# Project.net
KiCad netlist of a schematic drawn in EAGLE
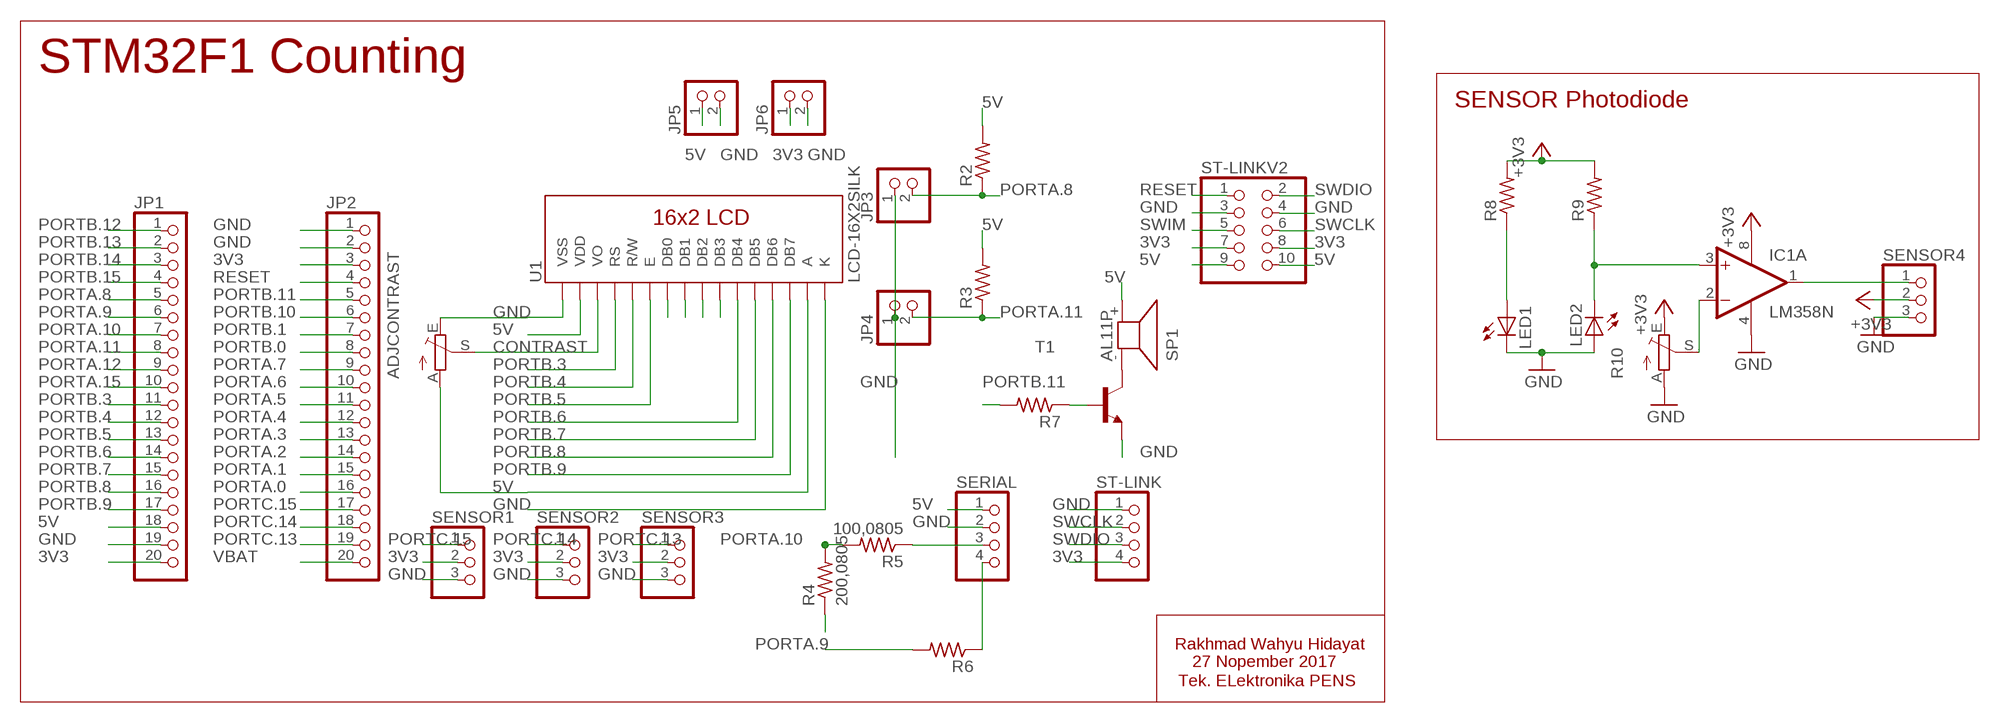
[diagram p0: schematic, sheet 1]

(export (version "E")
  (design (tool "Eeschema 10.0.6"))
  (components
    (comp (ref "ADJCONTRAST")
      (value "TRIM_EU-CA6V")
      (footprint "eagle-import:CA6V")
      (libsource (lib "eagle-import") (part "TRIM_EU-CA6V"))
    )
    (comp (ref "IC1")
      (value "LM358N")
      (footprint "eagle-import:DIL08")
      (libsource (lib "eagle-import") (part "LM358N"))
    )
    (comp (ref "JP1")
      (value "PINHD-1X20")
      (footprint "eagle-import:1X20")
      (libsource (lib "eagle-import") (part "PINHD-1X20"))
    )
    (comp (ref "JP2")
      (value "PINHD-1X20")
      (footprint "eagle-import:1X20")
      (libsource (lib "eagle-import") (part "PINHD-1X20"))
    )
    (comp (ref "JP3")
      (value "PINHD-1X2")
      (footprint "eagle-import:1X02")
      (libsource (lib "eagle-import") (part "PINHD-1X2"))
    )
    (comp (ref "JP4")
      (value "PINHD-1X2")
      (footprint "eagle-import:1X02")
      (libsource (lib "eagle-import") (part "PINHD-1X2"))
    )
    (comp (ref "JP5")
      (value "PINHD-1X2")
      (footprint "eagle-import:1X02")
      (libsource (lib "eagle-import") (part "PINHD-1X2"))
    )
    (comp (ref "JP6")
      (value "PINHD-1X2")
      (footprint "eagle-import:1X02")
      (libsource (lib "eagle-import") (part "PINHD-1X2"))
    )
    (comp (ref "LED1")
      (value "LED3MM")
      (footprint "eagle-import:LED3MM")
      (libsource (lib "eagle-import") (part "LED3MM"))
    )
    (comp (ref "LED2")
      (value "LED3MM")
      (footprint "eagle-import:LED3MM")
      (libsource (lib "eagle-import") (part "LED3MM"))
    )
    (comp (ref "R2")
      (value "R-US_M0805")
      (footprint "eagle-import:M0805")
      (libsource (lib "eagle-import") (part "R-US_M0805"))
    )
    (comp (ref "R3")
      (value "R-US_M0805")
      (footprint "eagle-import:M0805")
      (libsource (lib "eagle-import") (part "R-US_M0805"))
    )
    (comp (ref "R4")
      (value "200,0805")
      (footprint "eagle-import:M0805")
      (libsource (lib "eagle-import") (part "R-US_M0805"))
    )
    (comp (ref "R5")
      (value "100,0805")
      (footprint "eagle-import:M0805")
      (libsource (lib "eagle-import") (part "R-US_M0805"))
    )
    (comp (ref "R6")
      (value "R-US_M0805")
      (footprint "eagle-import:M0805")
      (libsource (lib "eagle-import") (part "R-US_M0805"))
    )
    (comp (ref "R7")
      (value "R-US_M0805")
      (footprint "eagle-import:M0805")
      (libsource (lib "eagle-import") (part "R-US_M0805"))
    )
    (comp (ref "R8")
      (value "R-US_0204/7")
      (footprint "eagle-import:0204_7")
      (libsource (lib "eagle-import") (part "R-US_0204/7"))
    )
    (comp (ref "R9")
      (value "R-US_0204/7")
      (footprint "eagle-import:0204_7")
      (libsource (lib "eagle-import") (part "R-US_0204/7"))
    )
    (comp (ref "R10")
      (value "TRIM_EU-CA6V")
      (footprint "eagle-import:CA6V")
      (libsource (lib "eagle-import") (part "TRIM_EU-CA6V"))
    )
    (comp (ref "SENSOR1")
      (value "PINHD-1X3")
      (footprint "eagle-import:1X03")
      (libsource (lib "eagle-import") (part "PINHD-1X3"))
    )
    (comp (ref "SENSOR2")
      (value "PINHD-1X3")
      (footprint "eagle-import:1X03")
      (libsource (lib "eagle-import") (part "PINHD-1X3"))
    )
    (comp (ref "SENSOR3")
      (value "PINHD-1X3")
      (footprint "eagle-import:1X03")
      (libsource (lib "eagle-import") (part "PINHD-1X3"))
    )
    (comp (ref "SENSOR4")
      (value "PINHD-1X3")
      (footprint "eagle-import:1X03")
      (libsource (lib "eagle-import") (part "PINHD-1X3"))
    )
    (comp (ref "SERIAL")
      (value "PINHD-1X4")
      (footprint "eagle-import:1X04")
      (libsource (lib "eagle-import") (part "PINHD-1X4"))
    )
    (comp (ref "SP1")
      (value "AL11P")
      (footprint "eagle-import:AL11P")
      (libsource (lib "eagle-import") (part "AL11P"))
    )
    (comp (ref "ST-LINK")
      (value "PINHD-1X4")
      (footprint "eagle-import:1X04")
      (libsource (lib "eagle-import") (part "PINHD-1X4"))
    )
    (comp (ref "ST-LINKV2")
      (value "PINHD-2X5")
      (footprint "eagle-import:2X05")
      (libsource (lib "eagle-import") (part "PINHD-2X5"))
    )
    (comp (ref "T1")
      (value "-NPN-SOT23-EBC")
      (footprint "eagle-import:SOT23-EBC")
      (libsource (lib "eagle-import") (part "-NPN-SOT23-EBC"))
    )
    (comp (ref "U1")
      (value "LCD-16X2SILK")
      (footprint "eagle-import:LCD-16X2")
      (libsource (lib "eagle-import") (part "LCD-16X2SILK"))
    )
  )
  (nets
    (net (code "1") (name "+3V3") (class "Default")
      (node (ref "IC1") (pin "8") (pinfunction "V+_8") (pintype "power_in"))
      (node (ref "R10") (pin "E") (pinfunction "E_E") (pintype "passive"))
      (node (ref "R8") (pin "2") (pinfunction "2_2") (pintype "passive"))
      (node (ref "R9") (pin "2") (pinfunction "2_2") (pintype "passive"))
      (node (ref "SENSOR4") (pin "2") (pinfunction "2_2") (pintype "passive"))
    )
    (net (code "2") (name "/3V3") (class "Default")
      (node (ref "JP1") (pin "20") (pinfunction "20_20") (pintype "passive"))
      (node (ref "JP2") (pin "3") (pinfunction "3_3") (pintype "passive"))
      (node (ref "JP6") (pin "1") (pinfunction "1_1") (pintype "passive"))
      (node (ref "SENSOR1") (pin "2") (pinfunction "2_2") (pintype "passive"))
      (node (ref "SENSOR2") (pin "2") (pinfunction "2_2") (pintype "passive"))
      (node (ref "SENSOR3") (pin "2") (pinfunction "2_2") (pintype "passive"))
      (node (ref "ST-LINK") (pin "4") (pinfunction "4_4") (pintype "passive"))
      (node (ref "ST-LINKV2") (pin "7") (pinfunction "7_7") (pintype "passive"))
      (node (ref "ST-LINKV2") (pin "8") (pinfunction "8_8") (pintype "passive"))
    )
    (net (code "3") (name "/5V") (class "Default")
      (node (ref "ADJCONTRAST") (pin "A") (pinfunction "A_A") (pintype "passive"))
      (node (ref "JP1") (pin "18") (pinfunction "18_18") (pintype "passive"))
      (node (ref "JP5") (pin "1") (pinfunction "1_1") (pintype "passive"))
      (node (ref "R2") (pin "2") (pinfunction "2_2") (pintype "passive"))
      (node (ref "R3") (pin "2") (pinfunction "2_2") (pintype "passive"))
      (node (ref "SERIAL") (pin "1") (pinfunction "1_1") (pintype "passive"))
      (node (ref "SP1") (pin "+") (pinfunction "2_+") (pintype "passive"))
      (node (ref "ST-LINKV2") (pin "10") (pinfunction "10_10") (pintype "passive"))
      (node (ref "ST-LINKV2") (pin "9") (pinfunction "9_9") (pintype "passive"))
      (node (ref "U1") (pin "15") (pinfunction "A_15") (pintype "power_in"))
      (node (ref "U1") (pin "2") (pinfunction "VDD_2") (pintype "power_in"))
    )
    (net (code "4") (name "/CONTRAST") (class "Default")
      (node (ref "ADJCONTRAST") (pin "S") (pinfunction "S_S") (pintype "passive"))
      (node (ref "U1") (pin "3") (pinfunction "VO_3") (pintype "bidirectional"))
    )
    (net (code "5") (name "/PORTA.0") (class "Default")
      (node (ref "JP2") (pin "16") (pinfunction "16_16") (pintype "passive"))
    )
    (net (code "6") (name "/PORTA.1") (class "Default")
      (node (ref "JP2") (pin "15") (pinfunction "15_15") (pintype "passive"))
    )
    (net (code "7") (name "/PORTA.2") (class "Default")
      (node (ref "JP2") (pin "14") (pinfunction "14_14") (pintype "passive"))
    )
    (net (code "8") (name "/PORTA.3") (class "Default")
      (node (ref "JP2") (pin "13") (pinfunction "13_13") (pintype "passive"))
    )
    (net (code "9") (name "/PORTA.4") (class "Default")
      (node (ref "JP2") (pin "12") (pinfunction "12_12") (pintype "passive"))
    )
    (net (code "10") (name "/PORTA.5") (class "Default")
      (node (ref "JP2") (pin "11") (pinfunction "11_11") (pintype "passive"))
    )
    (net (code "11") (name "/PORTA.6") (class "Default")
      (node (ref "JP2") (pin "10") (pinfunction "10_10") (pintype "passive"))
    )
    (net (code "12") (name "/PORTA.7") (class "Default")
      (node (ref "JP2") (pin "9") (pinfunction "9_9") (pintype "passive"))
    )
    (net (code "13") (name "/PORTA.8") (class "Default")
      (node (ref "JP1") (pin "5") (pinfunction "5_5") (pintype "passive"))
      (node (ref "JP3") (pin "2") (pinfunction "2_2") (pintype "passive"))
      (node (ref "R2") (pin "1") (pinfunction "1_1") (pintype "passive"))
    )
    (net (code "14") (name "/PORTA.9") (class "Default")
      (node (ref "JP1") (pin "6") (pinfunction "6_6") (pintype "passive"))
      (node (ref "R6") (pin "2") (pinfunction "2_2") (pintype "passive"))
    )
    (net (code "15") (name "/PORTA.10") (class "Default")
      (node (ref "JP1") (pin "7") (pinfunction "7_7") (pintype "passive"))
      (node (ref "R4") (pin "2") (pinfunction "2_2") (pintype "passive"))
      (node (ref "R5") (pin "2") (pinfunction "2_2") (pintype "passive"))
    )
    (net (code "16") (name "/PORTA.11") (class "Default")
      (node (ref "JP1") (pin "8") (pinfunction "8_8") (pintype "passive"))
      (node (ref "JP4") (pin "2") (pinfunction "2_2") (pintype "passive"))
      (node (ref "R3") (pin "1") (pinfunction "1_1") (pintype "passive"))
    )
    (net (code "17") (name "/PORTA.12") (class "Default")
      (node (ref "JP1") (pin "9") (pinfunction "9_9") (pintype "passive"))
    )
    (net (code "18") (name "/PORTA.15") (class "Default")
      (node (ref "JP1") (pin "10") (pinfunction "10_10") (pintype "passive"))
    )
    (net (code "19") (name "/PORTB.0") (class "Default")
      (node (ref "JP2") (pin "8") (pinfunction "8_8") (pintype "passive"))
    )
    (net (code "20") (name "/PORTB.1") (class "Default")
      (node (ref "JP2") (pin "7") (pinfunction "7_7") (pintype "passive"))
    )
    (net (code "21") (name "/PORTB.3") (class "Default")
      (node (ref "JP1") (pin "11") (pinfunction "11_11") (pintype "passive"))
      (node (ref "U1") (pin "4") (pinfunction "RS_4") (pintype "input"))
    )
    (net (code "22") (name "/PORTB.4") (class "Default")
      (node (ref "JP1") (pin "12") (pinfunction "12_12") (pintype "passive"))
      (node (ref "U1") (pin "5") (pinfunction "R/W_5") (pintype "input"))
    )
    (net (code "23") (name "/PORTB.5") (class "Default")
      (node (ref "JP1") (pin "13") (pinfunction "13_13") (pintype "passive"))
      (node (ref "U1") (pin "6") (pinfunction "E_6") (pintype "input"))
    )
    (net (code "24") (name "/PORTB.6") (class "Default")
      (node (ref "JP1") (pin "14") (pinfunction "14_14") (pintype "passive"))
      (node (ref "U1") (pin "11") (pinfunction "DB4_11") (pintype "bidirectional"))
    )
    (net (code "25") (name "/PORTB.7") (class "Default")
      (node (ref "JP1") (pin "15") (pinfunction "15_15") (pintype "passive"))
      (node (ref "U1") (pin "12") (pinfunction "DB5_12") (pintype "bidirectional"))
    )
    (net (code "26") (name "/PORTB.8") (class "Default")
      (node (ref "JP1") (pin "16") (pinfunction "16_16") (pintype "passive"))
      (node (ref "U1") (pin "13") (pinfunction "DB6_13") (pintype "bidirectional"))
    )
    (net (code "27") (name "/PORTB.9") (class "Default")
      (node (ref "JP1") (pin "17") (pinfunction "17_17") (pintype "passive"))
      (node (ref "U1") (pin "14") (pinfunction "DB7_14") (pintype "bidirectional"))
    )
    (net (code "28") (name "/PORTB.10") (class "Default")
      (node (ref "JP2") (pin "6") (pinfunction "6_6") (pintype "passive"))
    )
    (net (code "29") (name "/PORTB.11") (class "Default")
      (node (ref "JP2") (pin "5") (pinfunction "5_5") (pintype "passive"))
      (node (ref "R7") (pin "2") (pinfunction "2_2") (pintype "passive"))
    )
    (net (code "30") (name "/PORTB.12") (class "Default")
      (node (ref "JP1") (pin "1") (pinfunction "1_1") (pintype "passive"))
    )
    (net (code "31") (name "/PORTB.13") (class "Default")
      (node (ref "JP1") (pin "2") (pinfunction "2_2") (pintype "passive"))
    )
    (net (code "32") (name "/PORTB.14") (class "Default")
      (node (ref "JP1") (pin "3") (pinfunction "3_3") (pintype "passive"))
    )
    (net (code "33") (name "/PORTB.15") (class "Default")
      (node (ref "JP1") (pin "4") (pinfunction "4_4") (pintype "passive"))
    )
    (net (code "34") (name "/PORTC.13") (class "Default")
      (node (ref "JP2") (pin "19") (pinfunction "19_19") (pintype "passive"))
      (node (ref "SENSOR3") (pin "1") (pinfunction "1_1") (pintype "passive"))
    )
    (net (code "35") (name "/PORTC.14") (class "Default")
      (node (ref "JP2") (pin "18") (pinfunction "18_18") (pintype "passive"))
      (node (ref "SENSOR2") (pin "1") (pinfunction "1_1") (pintype "passive"))
    )
    (net (code "36") (name "/PORTC.15") (class "Default")
      (node (ref "JP2") (pin "17") (pinfunction "17_17") (pintype "passive"))
      (node (ref "SENSOR1") (pin "1") (pinfunction "1_1") (pintype "passive"))
    )
    (net (code "37") (name "/RESET") (class "Default")
      (node (ref "JP2") (pin "4") (pinfunction "4_4") (pintype "passive"))
      (node (ref "ST-LINKV2") (pin "1") (pinfunction "1_1") (pintype "passive"))
    )
    (net (code "38") (name "/SWCLK") (class "Default")
      (node (ref "ST-LINK") (pin "2") (pinfunction "2_2") (pintype "passive"))
      (node (ref "ST-LINKV2") (pin "6") (pinfunction "6_6") (pintype "passive"))
    )
    (net (code "39") (name "/SWDIO") (class "Default")
      (node (ref "ST-LINK") (pin "3") (pinfunction "3_3") (pintype "passive"))
      (node (ref "ST-LINKV2") (pin "2") (pinfunction "2_2") (pintype "passive"))
    )
    (net (code "40") (name "/SWIM") (class "Default")
      (node (ref "ST-LINKV2") (pin "5") (pinfunction "5_5") (pintype "passive"))
    )
    (net (code "41") (name "/VBAT") (class "Default")
      (node (ref "JP2") (pin "20") (pinfunction "20_20") (pintype "passive"))
    )
    (net (code "42") (name "GND") (class "Default")
      (node (ref "ADJCONTRAST") (pin "E") (pinfunction "E_E") (pintype "passive"))
      (node (ref "IC1") (pin "4") (pinfunction "V-_4") (pintype "power_in"))
      (node (ref "JP1") (pin "19") (pinfunction "19_19") (pintype "passive"))
      (node (ref "JP2") (pin "1") (pinfunction "1_1") (pintype "passive"))
      (node (ref "JP2") (pin "2") (pinfunction "2_2") (pintype "passive"))
      (node (ref "JP3") (pin "1") (pinfunction "1_1") (pintype "passive"))
      (node (ref "JP4") (pin "1") (pinfunction "1_1") (pintype "passive"))
      (node (ref "JP5") (pin "2") (pinfunction "2_2") (pintype "passive"))
      (node (ref "JP6") (pin "2") (pinfunction "2_2") (pintype "passive"))
      (node (ref "LED1") (pin "K") (pinfunction "C_K") (pintype "passive"))
      (node (ref "LED2") (pin "A") (pinfunction "A_A") (pintype "passive"))
      (node (ref "R10") (pin "A") (pinfunction "A_A") (pintype "passive"))
      (node (ref "R4") (pin "1") (pinfunction "1_1") (pintype "passive"))
      (node (ref "SENSOR1") (pin "3") (pinfunction "3_3") (pintype "passive"))
      (node (ref "SENSOR2") (pin "3") (pinfunction "3_3") (pintype "passive"))
      (node (ref "SENSOR3") (pin "3") (pinfunction "3_3") (pintype "passive"))
      (node (ref "SENSOR4") (pin "3") (pinfunction "3_3") (pintype "passive"))
      (node (ref "SERIAL") (pin "2") (pinfunction "2_2") (pintype "passive"))
      (node (ref "ST-LINK") (pin "1") (pinfunction "1_1") (pintype "passive"))
      (node (ref "ST-LINKV2") (pin "3") (pinfunction "3_3") (pintype "passive"))
      (node (ref "ST-LINKV2") (pin "4") (pinfunction "4_4") (pintype "passive"))
      (node (ref "T1") (pin "E") (pinfunction "E_E") (pintype "passive"))
      (node (ref "U1") (pin "1") (pinfunction "VSS_1") (pintype "power_in"))
      (node (ref "U1") (pin "16") (pinfunction "K_16") (pintype "power_in"))
    )
    (net (code "43") (name "Net-(IC1A-+IN)") (class "Default")
      (node (ref "IC1") (pin "3") (pinfunction "+IN_3") (pintype "input"))
      (node (ref "LED2") (pin "K") (pinfunction "C_K") (pintype "passive"))
      (node (ref "R9") (pin "1") (pinfunction "1_1") (pintype "passive"))
    )
    (net (code "44") (name "Net-(IC1A--IN)") (class "Default")
      (node (ref "IC1") (pin "2") (pinfunction "-IN_2") (pintype "input"))
      (node (ref "R10") (pin "S") (pinfunction "S_S") (pintype "passive"))
    )
    (net (code "45") (name "Net-(IC1A-OUT)") (class "Default")
      (node (ref "IC1") (pin "1") (pinfunction "OUT_1") (pintype "output"))
      (node (ref "SENSOR4") (pin "1") (pinfunction "1_1") (pintype "passive"))
    )
    (net (code "46") (name "Net-(LED1-PadA)") (class "Default")
      (node (ref "LED1") (pin "A") (pinfunction "A_A") (pintype "passive"))
      (node (ref "R8") (pin "1") (pinfunction "1_1") (pintype "passive"))
    )
    (net (code "47") (name "Net-(R5-Pad1)") (class "Default")
      (node (ref "R5") (pin "1") (pinfunction "1_1") (pintype "passive"))
      (node (ref "SERIAL") (pin "3") (pinfunction "3_3") (pintype "passive"))
    )
    (net (code "48") (name "Net-(R6-Pad1)") (class "Default")
      (node (ref "R6") (pin "1") (pinfunction "1_1") (pintype "passive"))
      (node (ref "SERIAL") (pin "4") (pinfunction "4_4") (pintype "passive"))
    )
    (net (code "49") (name "Net-(R7-Pad1)") (class "Default")
      (node (ref "R7") (pin "1") (pinfunction "1_1") (pintype "passive"))
      (node (ref "T1") (pin "B") (pinfunction "B_B") (pintype "passive"))
    )
    (net (code "50") (name "Net-(SP1-1)") (class "Default")
      (node (ref "SP1") (pin "-") (pinfunction "1_-") (pintype "passive"))
      (node (ref "T1") (pin "C") (pinfunction "C_C") (pintype "passive"))
    )
    (net (code "51") (name "unconnected-(U1-DB0-Pad7)") (class "Default")
      (node (ref "U1") (pin "7") (pinfunction "DB0_7") (pintype "bidirectional"))
    )
    (net (code "52") (name "unconnected-(U1-DB1-Pad8)") (class "Default")
      (node (ref "U1") (pin "8") (pinfunction "DB1_8") (pintype "bidirectional"))
    )
    (net (code "53") (name "unconnected-(U1-DB2-Pad9)") (class "Default")
      (node (ref "U1") (pin "9") (pinfunction "DB2_9") (pintype "bidirectional"))
    )
    (net (code "54") (name "unconnected-(U1-DB3-Pad10)") (class "Default")
      (node (ref "U1") (pin "10") (pinfunction "DB3_10") (pintype "bidirectional"))
    )
  )
)
